# CATS-Vega-GNSS.net
KiCad netlist of a schematic drawn in Altium Designer
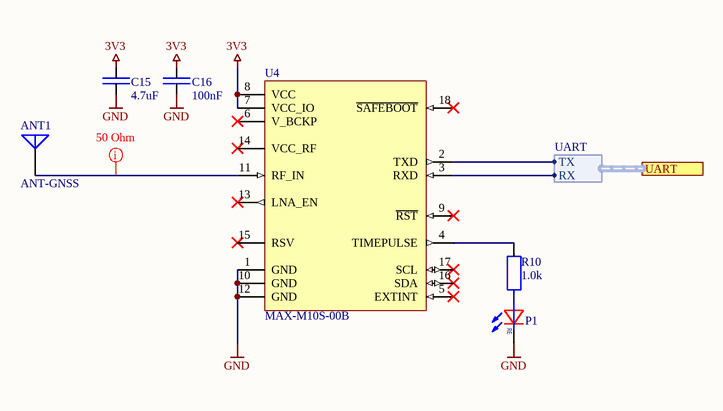
[diagram p0: CATS-Vega-GNSS.SchDoc]

(export (version "E")
  (design (tool "Eeschema 10.0.6"))
  (components
    (comp (ref "ANT1")
      (value "ANT-GNSS")
      (footprint "THT Antenna GNSS 18x18")
      (libsource (lib "RF") (part "ANT-GNSS"))
    )
    (comp (ref "C15")
      (value "4.7uF")
      (footprint "SMD Keramikkondensator 0603")
      (description "SMD Ceramic Capacitor E6")
      (libsource (lib "CATS-EUROC") (part "E6 - 4.7uF"))
    )
    (comp (ref "C16")
      (value "100nF")
      (footprint "SMD Keramikkondensator 0603")
      (description "SMD Ceramic Capacitor E6")
      (libsource (lib "CATS-EUROC") (part "E6 - 100nF"))
    )
    (comp (ref "P1")
      (value "LED")
      (footprint "SMD LED 0603")
      (description "Color LED")
      (libsource (lib "Diodes") (part "LED"))
    )
    (comp (ref "R10")
      (value "1.0k")
      (footprint "SMD Widerstand 0603")
      (description "SMD Chip Resistor E24")
      (libsource (lib "CATS-EUROC") (part "E24 - 1.0k"))
    )
    (comp (ref "U4")
      (value "MAX-M10S-00B")
      (footprint "SMD MAX-8")
      (description "u-blox 8 GNSS modules")
      (libsource (lib "Sensors") (part "MAX-M10S-00B"))
    )
  )
  (nets
    (net (code "2") (name "/RX") (class "Default")
      (node (ref "U4") (pin "3") (pinfunction "RXD_3") (pintype "input"))
    )
    (net (code "3") (name "/TX") (class "Default")
      (node (ref "U4") (pin "2") (pinfunction "TXD_2") (pintype "output"))
    )
    (net (code "5") (name "3V3") (class "Default")
      (node (ref "C15") (pin "2") (pinfunction "2_2") (pintype "passive"))
      (node (ref "C16") (pin "2") (pinfunction "2_2") (pintype "passive"))
      (node (ref "U4") (pin "7") (pinfunction "VCC_IO_7") (pintype "passive"))
      (node (ref "U4") (pin "8") (pinfunction "VCC_8") (pintype "passive"))
    )
    (net (code "6") (name "GND") (class "Default")
      (node (ref "C15") (pin "1") (pinfunction "1_1") (pintype "passive"))
      (node (ref "C16") (pin "1") (pinfunction "1_1") (pintype "passive"))
      (node (ref "P1") (pin "K") (pinfunction "K_K") (pintype "passive"))
      (node (ref "U4") (pin "1") (pinfunction "GND_1") (pintype "passive"))
      (node (ref "U4") (pin "10") (pinfunction "GND_10") (pintype "passive"))
      (node (ref "U4") (pin "12") (pinfunction "GND_12") (pintype "passive"))
    )
    (net (code "7") (name "Net-(P1-PadA)") (class "Default")
      (node (ref "P1") (pin "A") (pinfunction "A_A") (pintype "passive"))
      (node (ref "R10") (pin "1") (pinfunction "1_1") (pintype "passive"))
    )
    (net (code "8") (name "Net-(U4-RF_IN)") (class "Default")
      (node (ref "ANT1") (pin "1") (pinfunction "1_1") (pintype "passive"))
      (node (ref "U4") (pin "11") (pinfunction "RF_IN_11") (pintype "input"))
    )
    (net (code "9") (name "Net-(U4-TIMEPULSE)") (class "Default")
      (node (ref "R10") (pin "2") (pinfunction "2_2") (pintype "passive"))
      (node (ref "U4") (pin "4") (pinfunction "TIMEPULSE_4") (pintype "output"))
    )
    (net (code "10") (name "unconnected-(U4-EXTINT-Pad5)") (class "Default")
      (node (ref "U4") (pin "5") (pinfunction "EXTINT_5") (pintype "input+no_connect"))
    )
    (net (code "11") (name "unconnected-(U4-LNA_EN-Pad13)") (class "Default")
      (node (ref "U4") (pin "13") (pinfunction "LNA_EN_13") (pintype "output+no_connect"))
    )
    (net (code "12") (name "unconnected-(U4-RSV-Pad15)") (class "Default")
      (node (ref "U4") (pin "15") (pinfunction "RSV_15") (pintype "passive+no_connect"))
    )
    (net (code "13") (name "unconnected-(U4-SCL-Pad17)") (class "Default")
      (node (ref "U4") (pin "17") (pinfunction "SCL_17") (pintype "bidirectional+no_connect"))
    )
    (net (code "14") (name "unconnected-(U4-SDA-Pad16)") (class "Default")
      (node (ref "U4") (pin "16") (pinfunction "SDA_16") (pintype "bidirectional+no_connect"))
    )
    (net (code "15") (name "unconnected-(U4-VCC_RF-Pad14)") (class "Default")
      (node (ref "U4") (pin "14") (pinfunction "VCC_RF_14") (pintype "passive+no_connect"))
    )
    (net (code "16") (name "unconnected-(U4-V_BCKP-Pad6)") (class "Default")
      (node (ref "U4") (pin "6") (pinfunction "V_BCKP_6") (pintype "passive+no_connect"))
    )
    (net (code "17") (name "unconnected-(U4-~{RST}-Pad9)") (class "Default")
      (node (ref "U4") (pin "9") (pinfunction "~{RST}_9") (pintype "input+no_connect"))
    )
    (net (code "18") (name "unconnected-(U4-~{SAFEBOOT}-Pad18)") (class "Default")
      (node (ref "U4") (pin "18") (pinfunction "~{SAFEBOOT}_18") (pintype "input+no_connect"))
    )
  )
)
